# PWR.net
KiCad netlist of a schematic drawn in Altium Designer
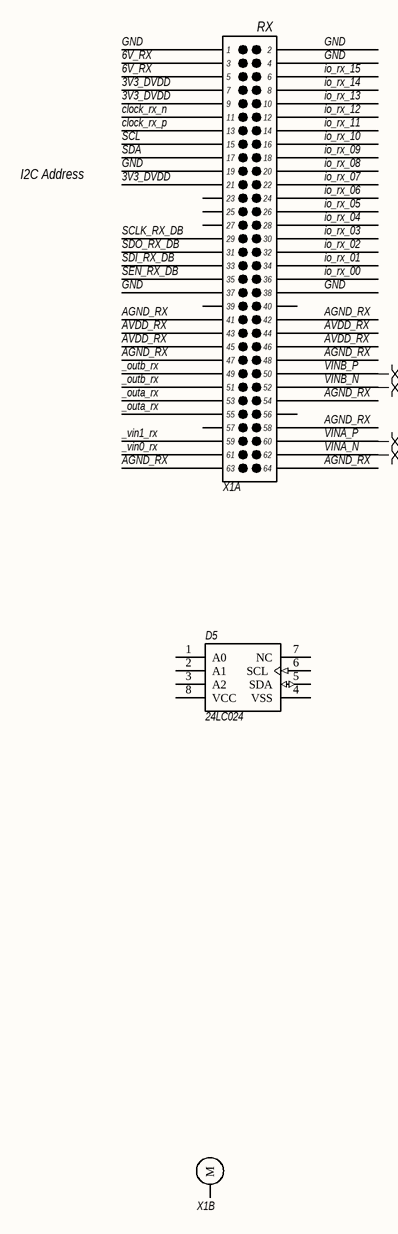
[diagram p0: PWR.SchDoc]

(export (version "E")
  (design (tool "Eeschema 10.0.6"))
  (components
    (comp (ref "D5")
      (value "24LC024")
      (footprint "SOIC_SN8")
      (description "I2C EEPROM")
      (fields (field (name "MANUFACTURER") "Microchip") (field (name "VOLTAGE") "2.5-5.5V"))
      (libsource (lib "Kintex_SDR") (part "24LC024"))
    )
    (comp (ref "X1")
      (value "DBoard")
      (footprint "DBLib:DBoard")
      (description "USRP DBoard")
      (fields (field (name "MANUFACTURER") "Molex"))
      (libsource (lib "DBLib") (part "DBoard"))
    )
  )
  (nets
    (net (code "1") (name "/3V3_DVDD") (class "Default")
      (node (ref "X1") (pin "71") (pinfunction "7_71") (pintype "passive"))
      (node (ref "X1") (pin "73") (pinfunction "9_73") (pintype "passive"))
      (node (ref "X1") (pin "85") (pinfunction "21_85") (pintype "passive"))
    )
    (net (code "2") (name "/6V_RX") (class "Default")
      (node (ref "X1") (pin "67") (pinfunction "3_67") (pintype "passive"))
      (node (ref "X1") (pin "69") (pinfunction "5_69") (pintype "passive"))
    )
    (net (code "3") (name "/AGND_RX") (class "Default")
      (node (ref "X1") (pin "105") (pinfunction "41_105") (pintype "passive"))
      (node (ref "X1") (pin "106") (pinfunction "42_106") (pintype "passive"))
      (node (ref "X1") (pin "111") (pinfunction "47_111") (pintype "passive"))
      (node (ref "X1") (pin "112") (pinfunction "48_112") (pintype "passive"))
      (node (ref "X1") (pin "118") (pinfunction "54_118") (pintype "passive"))
      (node (ref "X1") (pin "122") (pinfunction "58_122") (pintype "passive"))
      (node (ref "X1") (pin "127") (pinfunction "63_127") (pintype "passive"))
      (node (ref "X1") (pin "128") (pinfunction "64_128") (pintype "passive"))
    )
    (net (code "4") (name "/AVDD_RX") (class "Default")
      (node (ref "X1") (pin "107") (pinfunction "43_107") (pintype "passive"))
      (node (ref "X1") (pin "108") (pinfunction "44_108") (pintype "passive"))
      (node (ref "X1") (pin "109") (pinfunction "45_109") (pintype "passive"))
      (node (ref "X1") (pin "110") (pinfunction "46_110") (pintype "passive"))
    )
    (net (code "5") (name "/GND") (class "Default")
      (node (ref "X1") (pin "101") (pinfunction "37_101") (pintype "passive"))
      (node (ref "X1") (pin "102") (pinfunction "38_102") (pintype "passive"))
      (node (ref "X1") (pin "65") (pinfunction "1_65") (pintype "passive"))
      (node (ref "X1") (pin "66") (pinfunction "2_66") (pintype "passive"))
      (node (ref "X1") (pin "68") (pinfunction "4_68") (pintype "passive"))
      (node (ref "X1") (pin "83") (pinfunction "19_83") (pintype "passive"))
    )
    (net (code "6") (name "/SCL") (class "Default")
      (node (ref "X1") (pin "79") (pinfunction "15_79") (pintype "passive"))
    )
    (net (code "7") (name "/SCLK_RX_DB") (class "Default")
      (node (ref "X1") (pin "93") (pinfunction "29_93") (pintype "passive"))
    )
    (net (code "8") (name "/SDA") (class "Default")
      (node (ref "X1") (pin "81") (pinfunction "17_81") (pintype "passive"))
    )
    (net (code "9") (name "/SDI_RX_DB") (class "Default")
      (node (ref "X1") (pin "97") (pinfunction "33_97") (pintype "passive"))
    )
    (net (code "10") (name "/SDO_RX_DB") (class "Default")
      (node (ref "X1") (pin "95") (pinfunction "31_95") (pintype "passive"))
    )
    (net (code "11") (name "/SEN_RX_DB") (class "Default")
      (node (ref "X1") (pin "99") (pinfunction "35_99") (pintype "passive"))
    )
    (net (code "12") (name "/VINA_N") (class "Default")
      (node (ref "X1") (pin "126") (pinfunction "62_126") (pintype "passive"))
    )
    (net (code "13") (name "/VINA_P") (class "Default")
      (node (ref "X1") (pin "124") (pinfunction "60_124") (pintype "passive"))
    )
    (net (code "14") (name "/VINB_N") (class "Default")
      (node (ref "X1") (pin "116") (pinfunction "52_116") (pintype "passive"))
    )
    (net (code "15") (name "/VINB_P") (class "Default")
      (node (ref "X1") (pin "114") (pinfunction "50_114") (pintype "passive"))
    )
    (net (code "16") (name "/_outa_rx") (class "Default")
      (node (ref "X1") (pin "117") (pinfunction "53_117") (pintype "passive"))
      (node (ref "X1") (pin "119") (pinfunction "55_119") (pintype "passive"))
    )
    (net (code "17") (name "/_outb_rx") (class "Default")
      (node (ref "X1") (pin "113") (pinfunction "49_113") (pintype "passive"))
      (node (ref "X1") (pin "115") (pinfunction "51_115") (pintype "passive"))
    )
    (net (code "18") (name "/_vin0_rx") (class "Default")
      (node (ref "X1") (pin "125") (pinfunction "61_125") (pintype "passive"))
    )
    (net (code "19") (name "/_vin1_rx") (class "Default")
      (node (ref "X1") (pin "123") (pinfunction "59_123") (pintype "passive"))
    )
    (net (code "20") (name "/clock_rx_n") (class "Default")
      (node (ref "X1") (pin "75") (pinfunction "11_75") (pintype "passive"))
    )
    (net (code "21") (name "/clock_rx_p") (class "Default")
      (node (ref "X1") (pin "77") (pinfunction "13_77") (pintype "passive"))
    )
    (net (code "22") (name "/io_rx_00") (class "Default")
      (node (ref "X1") (pin "100") (pinfunction "36_100") (pintype "passive"))
    )
    (net (code "23") (name "/io_rx_01") (class "Default")
      (node (ref "X1") (pin "98") (pinfunction "34_98") (pintype "passive"))
    )
    (net (code "24") (name "/io_rx_02") (class "Default")
      (node (ref "X1") (pin "96") (pinfunction "32_96") (pintype "passive"))
    )
    (net (code "25") (name "/io_rx_03") (class "Default")
      (node (ref "X1") (pin "94") (pinfunction "30_94") (pintype "passive"))
    )
    (net (code "26") (name "/io_rx_04") (class "Default")
      (node (ref "X1") (pin "92") (pinfunction "28_92") (pintype "passive"))
    )
    (net (code "27") (name "/io_rx_05") (class "Default")
      (node (ref "X1") (pin "90") (pinfunction "26_90") (pintype "passive"))
    )
    (net (code "28") (name "/io_rx_06") (class "Default")
      (node (ref "X1") (pin "88") (pinfunction "24_88") (pintype "passive"))
    )
    (net (code "29") (name "/io_rx_07") (class "Default")
      (node (ref "X1") (pin "86") (pinfunction "22_86") (pintype "passive"))
    )
    (net (code "30") (name "/io_rx_08") (class "Default")
      (node (ref "X1") (pin "84") (pinfunction "20_84") (pintype "passive"))
    )
    (net (code "31") (name "/io_rx_09") (class "Default")
      (node (ref "X1") (pin "82") (pinfunction "18_82") (pintype "passive"))
    )
    (net (code "32") (name "/io_rx_10") (class "Default")
      (node (ref "X1") (pin "80") (pinfunction "16_80") (pintype "passive"))
    )
    (net (code "33") (name "/io_rx_11") (class "Default")
      (node (ref "X1") (pin "78") (pinfunction "14_78") (pintype "passive"))
    )
    (net (code "34") (name "/io_rx_12") (class "Default")
      (node (ref "X1") (pin "76") (pinfunction "12_76") (pintype "passive"))
    )
    (net (code "35") (name "/io_rx_13") (class "Default")
      (node (ref "X1") (pin "74") (pinfunction "10_74") (pintype "passive"))
    )
    (net (code "36") (name "/io_rx_14") (class "Default")
      (node (ref "X1") (pin "72") (pinfunction "8_72") (pintype "passive"))
    )
    (net (code "37") (name "/io_rx_15") (class "Default")
      (node (ref "X1") (pin "70") (pinfunction "6_70") (pintype "passive"))
    )
    (net (code "38") (name "unconnected-(D5-A0-Pad1)") (class "Default")
      (node (ref "D5") (pin "1") (pinfunction "A0_1") (pintype "passive"))
    )
    (net (code "39") (name "unconnected-(D5-A1-Pad2)") (class "Default")
      (node (ref "D5") (pin "2") (pinfunction "A1_2") (pintype "passive"))
    )
    (net (code "40") (name "unconnected-(D5-A2-Pad3)") (class "Default")
      (node (ref "D5") (pin "3") (pinfunction "A2_3") (pintype "passive"))
    )
    (net (code "41") (name "unconnected-(D5-NC-Pad7)") (class "Default")
      (node (ref "D5") (pin "7") (pinfunction "NC_7") (pintype "passive"))
    )
    (net (code "42") (name "unconnected-(D5-SCL-Pad6)") (class "Default")
      (node (ref "D5") (pin "6") (pinfunction "SCL_6") (pintype "input"))
    )
    (net (code "43") (name "unconnected-(D5-SDA-Pad5)") (class "Default")
      (node (ref "D5") (pin "5") (pinfunction "SDA_5") (pintype "bidirectional"))
    )
    (net (code "44") (name "unconnected-(D5-VCC-Pad8)") (class "Default")
      (node (ref "D5") (pin "8") (pinfunction "VCC_8") (pintype "power_in"))
    )
    (net (code "45") (name "unconnected-(D5-VSS-Pad4)") (class "Default")
      (node (ref "D5") (pin "4") (pinfunction "VSS_4") (pintype "power_in"))
    )
    (net (code "46") (name "unconnected-(X1A-23-Pad87)") (class "Default")
      (node (ref "X1") (pin "87") (pinfunction "23_87") (pintype "passive"))
    )
    (net (code "47") (name "unconnected-(X1A-25-Pad89)") (class "Default")
      (node (ref "X1") (pin "89") (pinfunction "25_89") (pintype "passive"))
    )
    (net (code "48") (name "unconnected-(X1A-27-Pad91)") (class "Default")
      (node (ref "X1") (pin "91") (pinfunction "27_91") (pintype "passive"))
    )
    (net (code "49") (name "unconnected-(X1A-39-Pad103)") (class "Default")
      (node (ref "X1") (pin "103") (pinfunction "39_103") (pintype "passive"))
    )
    (net (code "50") (name "unconnected-(X1A-40-Pad104)") (class "Default")
      (node (ref "X1") (pin "104") (pinfunction "40_104") (pintype "passive"))
    )
    (net (code "51") (name "unconnected-(X1A-56-Pad120)") (class "Default")
      (node (ref "X1") (pin "120") (pinfunction "56_120") (pintype "passive"))
    )
    (net (code "52") (name "unconnected-(X1A-57-Pad121)") (class "Default")
      (node (ref "X1") (pin "121") (pinfunction "57_121") (pintype "passive"))
    )
    (net (code "53") (name "unconnected-(X1B-M-Pad0)") (class "Default")
      (node (ref "X1") (pin "0") (pinfunction "M_0") (pintype "passive"))
    )
  )
)
